# AD8428_shield.net
KiCad netlist of a schematic drawn in Altium Designer
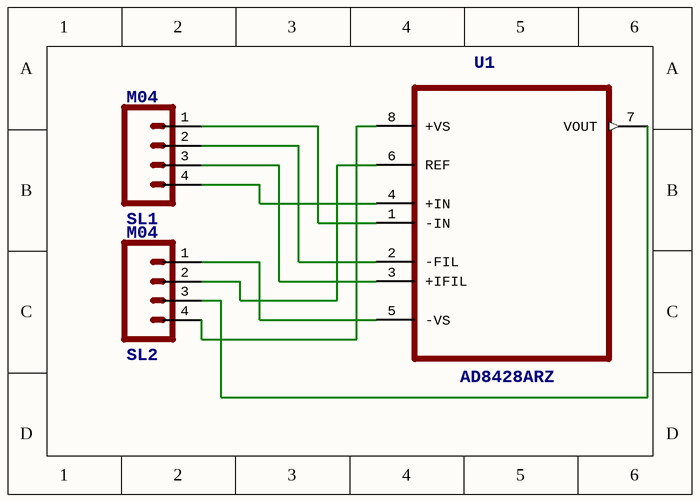
[diagram p0: AD8428_shield.SchDoc]

(export (version "E")
  (design (tool "Eeschema 10.0.6"))
  (components
    (comp (ref "SL1")
      (value "M04")
      (footprint "04P")
      (description "<b>AMP QUICK CONNECTOR</b>")
      (libsource (lib "con-amp-quick") (part "M04"))
    )
    (comp (ref "SL2")
      (value "M04")
      (footprint "04P")
      (description "<b>AMP QUICK CONNECTOR</b>")
      (libsource (lib "con-amp-quick") (part "M04"))
    )
    (comp (ref "U1")
      (value "AD8428ARZ")
      (footprint "SOIC127P600X175-8N")
      (description "Instrumentation Amplifier")
      (libsource (lib "AD8428") (part "AD8428ARZ"))
    )
  )
  (nets
    (net (code "1") (name "Net-(U1-+IFIL)") (class "Default")
      (node (ref "SL1") (pin "3") (pinfunction "3_3") (pintype "passive"))
      (node (ref "U1") (pin "3") (pinfunction "+IFIL_3") (pintype "passive"))
    )
    (net (code "2") (name "Net-(U1-+IN)") (class "Default")
      (node (ref "SL1") (pin "4") (pinfunction "4_4") (pintype "passive"))
      (node (ref "U1") (pin "4") (pinfunction "+IN_4") (pintype "passive"))
    )
    (net (code "3") (name "Net-(U1-+VS)") (class "Default")
      (node (ref "SL2") (pin "4") (pinfunction "4_4") (pintype "passive"))
      (node (ref "U1") (pin "8") (pinfunction "+VS_8") (pintype "power_in"))
    )
    (net (code "4") (name "Net-(U1--FIL)") (class "Default")
      (node (ref "SL1") (pin "2") (pinfunction "2_2") (pintype "passive"))
      (node (ref "U1") (pin "2") (pinfunction "-FIL_2") (pintype "passive"))
    )
    (net (code "5") (name "Net-(U1--IN)") (class "Default")
      (node (ref "SL1") (pin "1") (pinfunction "1_1") (pintype "passive"))
      (node (ref "U1") (pin "1") (pinfunction "-IN_1") (pintype "passive"))
    )
    (net (code "6") (name "Net-(U1--VS)") (class "Default")
      (node (ref "SL2") (pin "1") (pinfunction "1_1") (pintype "passive"))
      (node (ref "U1") (pin "5") (pinfunction "-VS_5") (pintype "power_in"))
    )
    (net (code "7") (name "Net-(U1-REF)") (class "Default")
      (node (ref "SL2") (pin "2") (pinfunction "2_2") (pintype "passive"))
      (node (ref "U1") (pin "6") (pinfunction "REF_6") (pintype "passive"))
    )
    (net (code "8") (name "Net-(U1-VOUT)") (class "Default")
      (node (ref "SL2") (pin "3") (pinfunction "3_3") (pintype "passive"))
      (node (ref "U1") (pin "7") (pinfunction "VOUT_7") (pintype "output"))
    )
  )
)
